# PFC_drivers_v1.net
KiCad netlist of a schematic drawn in EAGLE
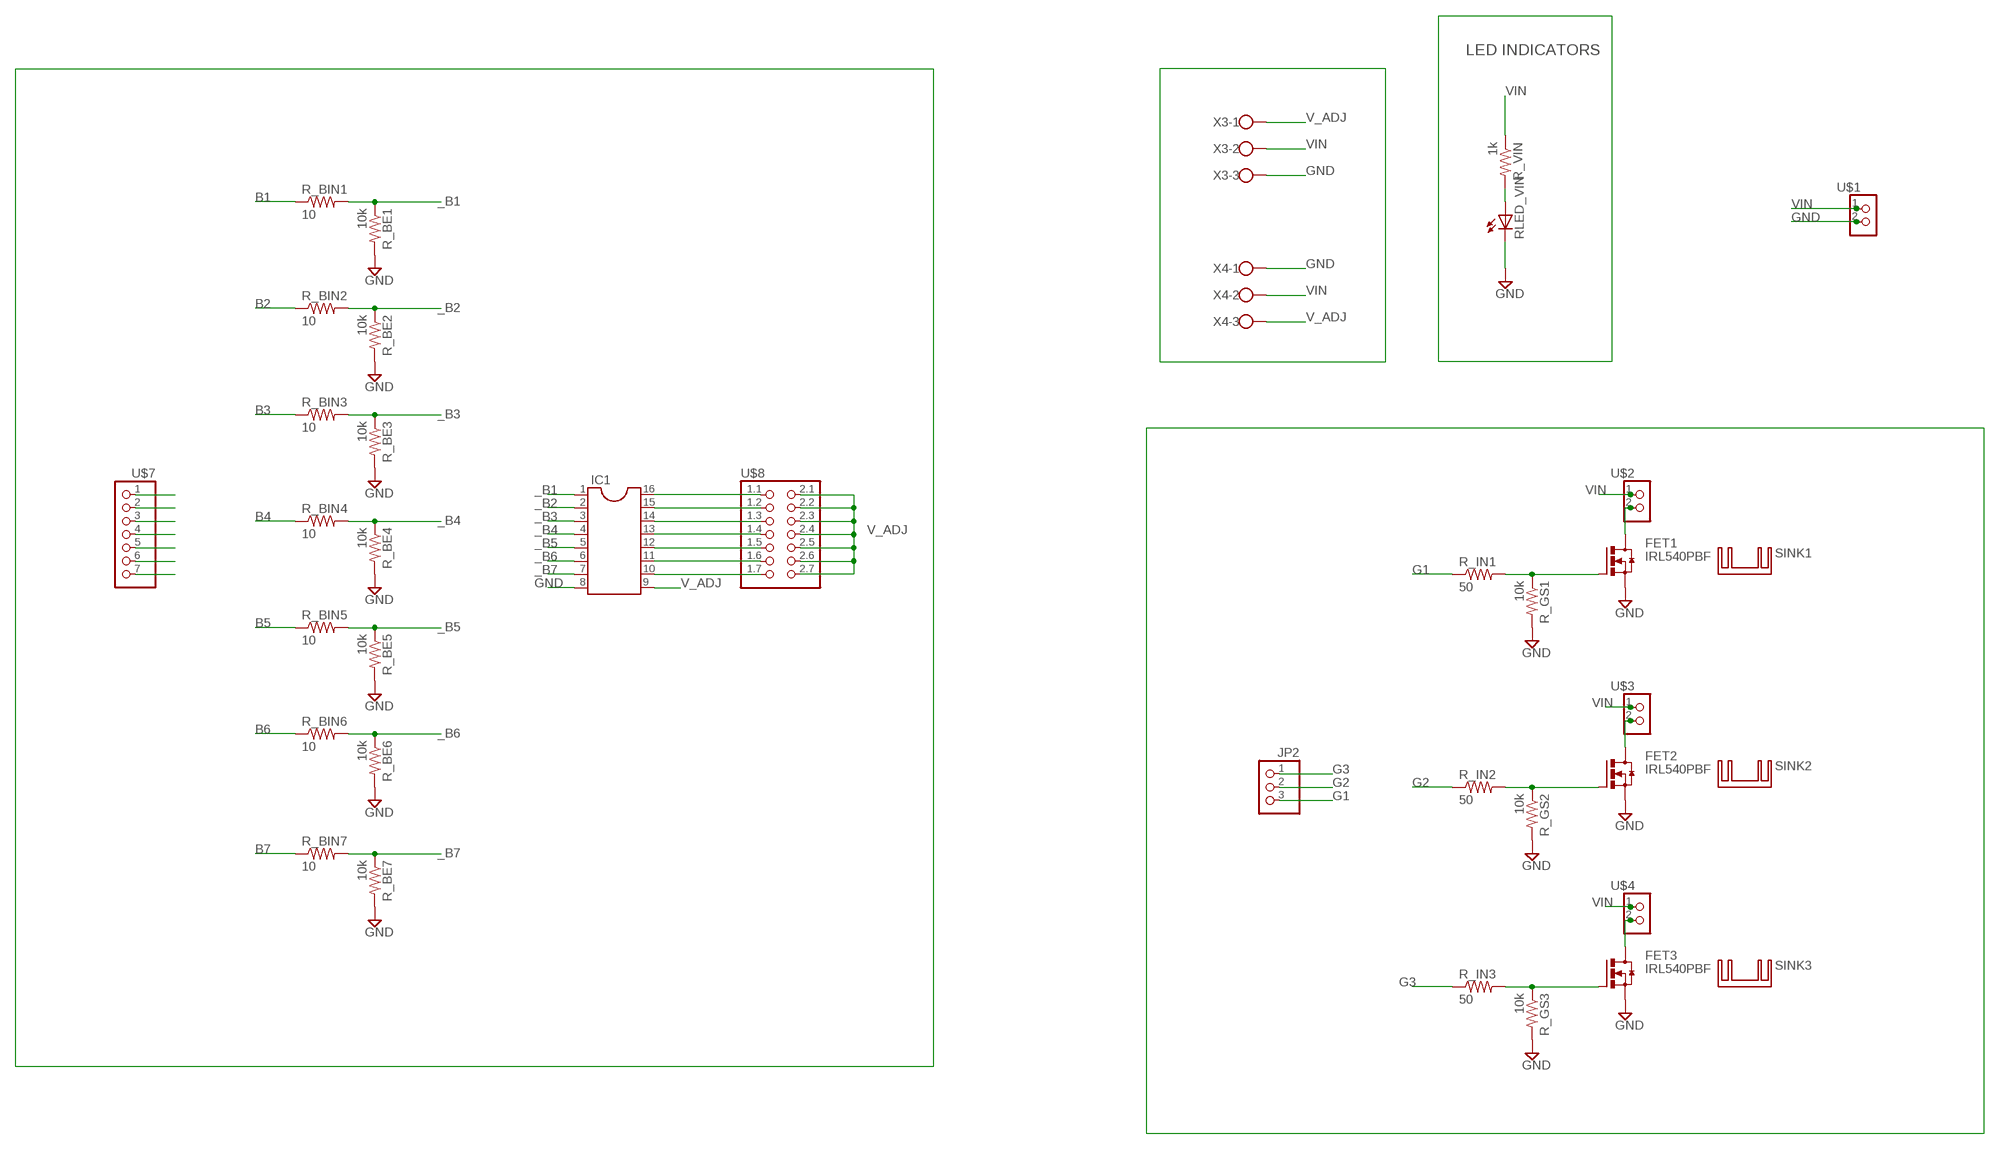
[diagram p0: schematic, sheet 1]

(export (version "E")
  (design (tool "Eeschema 10.0.6"))
  (components
    (comp (ref "FET1")
      (value "IRL540PBF")
      (footprint "eagle-import:TO220AV")
      (libsource (lib "eagle-import") (part "IRL540PBF"))
    )
    (comp (ref "FET2")
      (value "IRL540PBF")
      (footprint "eagle-import:TO220AV")
      (libsource (lib "eagle-import") (part "IRL540PBF"))
    )
    (comp (ref "FET3")
      (value "IRL540PBF")
      (footprint "eagle-import:TO220AV")
      (libsource (lib "eagle-import") (part "IRL540PBF"))
    )
    (comp (ref "IC1")
      (value "DIL16S")
      (footprint "eagle-import:SOCKET-16")
      (libsource (lib "eagle-import") (part "DIL16S"))
    )
    (comp (ref "JP2")
      (value "PINHD-1X3")
      (footprint "eagle-import:1X03")
      (libsource (lib "eagle-import") (part "PINHD-1X3"))
    )
    (comp (ref "RLED_VIN")
      (value "LEDCHIP-LED0603")
      (footprint "eagle-import:CHIP-LED0603")
      (libsource (lib "eagle-import") (part "LEDCHIP-LED0603"))
    )
    (comp (ref "R_BE1")
      (value "10k")
      (footprint "eagle-import:R0603")
      (libsource (lib "eagle-import") (part "R-US_R0603"))
    )
    (comp (ref "R_BE2")
      (value "10k")
      (footprint "eagle-import:R0603")
      (libsource (lib "eagle-import") (part "R-US_R0603"))
    )
    (comp (ref "R_BE3")
      (value "10k")
      (footprint "eagle-import:R0603")
      (libsource (lib "eagle-import") (part "R-US_R0603"))
    )
    (comp (ref "R_BE4")
      (value "10k")
      (footprint "eagle-import:R0603")
      (libsource (lib "eagle-import") (part "R-US_R0603"))
    )
    (comp (ref "R_BE5")
      (value "10k")
      (footprint "eagle-import:R0603")
      (libsource (lib "eagle-import") (part "R-US_R0603"))
    )
    (comp (ref "R_BE6")
      (value "10k")
      (footprint "eagle-import:R0603")
      (libsource (lib "eagle-import") (part "R-US_R0603"))
    )
    (comp (ref "R_BE7")
      (value "10k")
      (footprint "eagle-import:R0603")
      (libsource (lib "eagle-import") (part "R-US_R0603"))
    )
    (comp (ref "R_BIN1")
      (value "10")
      (footprint "eagle-import:R0603")
      (libsource (lib "eagle-import") (part "R-US_R0603"))
    )
    (comp (ref "R_BIN2")
      (value "10")
      (footprint "eagle-import:R0603")
      (libsource (lib "eagle-import") (part "R-US_R0603"))
    )
    (comp (ref "R_BIN3")
      (value "10")
      (footprint "eagle-import:R0603")
      (libsource (lib "eagle-import") (part "R-US_R0603"))
    )
    (comp (ref "R_BIN4")
      (value "10")
      (footprint "eagle-import:R0603")
      (libsource (lib "eagle-import") (part "R-US_R0603"))
    )
    (comp (ref "R_BIN5")
      (value "10")
      (footprint "eagle-import:R0603")
      (libsource (lib "eagle-import") (part "R-US_R0603"))
    )
    (comp (ref "R_BIN6")
      (value "10")
      (footprint "eagle-import:R0603")
      (libsource (lib "eagle-import") (part "R-US_R0603"))
    )
    (comp (ref "R_BIN7")
      (value "10")
      (footprint "eagle-import:R0603")
      (libsource (lib "eagle-import") (part "R-US_R0603"))
    )
    (comp (ref "R_GS1")
      (value "10k")
      (footprint "eagle-import:R0603")
      (libsource (lib "eagle-import") (part "R-US_R0603"))
    )
    (comp (ref "R_GS2")
      (value "10k")
      (footprint "eagle-import:R0603")
      (libsource (lib "eagle-import") (part "R-US_R0603"))
    )
    (comp (ref "R_GS3")
      (value "10k")
      (footprint "eagle-import:R0603")
      (libsource (lib "eagle-import") (part "R-US_R0603"))
    )
    (comp (ref "R_IN1")
      (value "50")
      (footprint "eagle-import:R0603")
      (libsource (lib "eagle-import") (part "R-US_R0603"))
    )
    (comp (ref "R_IN2")
      (value "50")
      (footprint "eagle-import:R0603")
      (libsource (lib "eagle-import") (part "R-US_R0603"))
    )
    (comp (ref "R_IN3")
      (value "50")
      (footprint "eagle-import:R0603")
      (libsource (lib "eagle-import") (part "R-US_R0603"))
    )
    (comp (ref "R_VIN")
      (value "1k")
      (footprint "eagle-import:R0603")
      (libsource (lib "eagle-import") (part "R-US_R0603"))
    )
    (comp (ref "SINK1")
      (value "FW1S")
      (footprint "eagle-import:FW1S")
      (libsource (lib "eagle-import") (part "FW1S"))
    )
    (comp (ref "SINK2")
      (value "FW1S")
      (footprint "eagle-import:FW1S")
      (libsource (lib "eagle-import") (part "FW1S"))
    )
    (comp (ref "SINK3")
      (value "FW1S")
      (footprint "eagle-import:FW1S")
      (libsource (lib "eagle-import") (part "FW1S"))
    )
    (comp (ref "U$1")
      (value "PINHD-2X1")
      (footprint "eagle-import:2X01")
      (libsource (lib "eagle-import") (part "PINHD-2X1"))
    )
    (comp (ref "U$2")
      (value "PINHD-2X1")
      (footprint "eagle-import:2X01")
      (libsource (lib "eagle-import") (part "PINHD-2X1"))
    )
    (comp (ref "U$3")
      (value "PINHD-2X1")
      (footprint "eagle-import:2X01")
      (libsource (lib "eagle-import") (part "PINHD-2X1"))
    )
    (comp (ref "U$4")
      (value "PINHD-2X1")
      (footprint "eagle-import:2X01")
      (libsource (lib "eagle-import") (part "PINHD-2X1"))
    )
    (comp (ref "U$7")
      (value "PINHD-1X7")
      (footprint "eagle-import:1X07")
      (libsource (lib "eagle-import") (part "PINHD-1X7"))
    )
    (comp (ref "U$8")
      (value "PINHD-2X7")
      (footprint "eagle-import:2X07-BIG")
      (libsource (lib "eagle-import") (part "PINHD-2X7"))
    )
    (comp (ref "X3")
      (value "W237-103")
      (footprint "eagle-import:W237-103")
      (fields (field (name "MPN") "237-103"))
      (libsource (lib "eagle-import") (part "W237-103"))
    )
    (comp (ref "X4")
      (value "W237-103")
      (footprint "eagle-import:W237-103")
      (fields (field (name "MPN") "237-103"))
      (libsource (lib "eagle-import") (part "W237-103"))
    )
  )
  (nets
    (net (code "1") (name "/B1") (class "Default")
      (node (ref "R_BIN1") (pin "1") (pinfunction "1_1") (pintype "passive"))
      (node (ref "U$7") (pin "1") (pinfunction "1_1") (pintype "passive"))
    )
    (net (code "2") (name "/B2") (class "Default")
      (node (ref "R_BIN2") (pin "1") (pinfunction "1_1") (pintype "passive"))
      (node (ref "U$7") (pin "2") (pinfunction "2_2") (pintype "passive"))
    )
    (net (code "3") (name "/B3") (class "Default")
      (node (ref "R_BIN3") (pin "1") (pinfunction "1_1") (pintype "passive"))
      (node (ref "U$7") (pin "3") (pinfunction "3_3") (pintype "passive"))
    )
    (net (code "4") (name "/B4") (class "Default")
      (node (ref "R_BIN4") (pin "1") (pinfunction "1_1") (pintype "passive"))
      (node (ref "U$7") (pin "4") (pinfunction "4_4") (pintype "passive"))
    )
    (net (code "5") (name "/B5") (class "Default")
      (node (ref "R_BIN5") (pin "1") (pinfunction "1_1") (pintype "passive"))
      (node (ref "U$7") (pin "5") (pinfunction "5_5") (pintype "passive"))
    )
    (net (code "6") (name "/B6") (class "Default")
      (node (ref "R_BIN6") (pin "1") (pinfunction "1_1") (pintype "passive"))
      (node (ref "U$7") (pin "6") (pinfunction "6_6") (pintype "passive"))
    )
    (net (code "7") (name "/B7") (class "Default")
      (node (ref "R_BIN7") (pin "1") (pinfunction "1_1") (pintype "passive"))
      (node (ref "U$7") (pin "7") (pinfunction "7_7") (pintype "passive"))
    )
    (net (code "8") (name "/G1") (class "Default")
      (node (ref "JP2") (pin "3") (pinfunction "3_3") (pintype "passive"))
      (node (ref "R_IN1") (pin "1") (pinfunction "1_1") (pintype "passive"))
    )
    (net (code "9") (name "/G2") (class "Default")
      (node (ref "JP2") (pin "2") (pinfunction "2_2") (pintype "passive"))
      (node (ref "R_IN2") (pin "1") (pinfunction "1_1") (pintype "passive"))
    )
    (net (code "10") (name "/G3") (class "Default")
      (node (ref "JP2") (pin "1") (pinfunction "1_1") (pintype "passive"))
      (node (ref "R_IN3") (pin "1") (pinfunction "1_1") (pintype "passive"))
    )
    (net (code "11") (name "/VIN") (class "Default")
      (node (ref "R_VIN") (pin "1") (pinfunction "1_1") (pintype "passive"))
      (node (ref "U$1") (pin "1") (pinfunction "1_1") (pintype "passive"))
      (node (ref "U$2") (pin "1") (pinfunction "1_1") (pintype "passive"))
      (node (ref "U$3") (pin "1") (pinfunction "1_1") (pintype "passive"))
      (node (ref "U$4") (pin "1") (pinfunction "1_1") (pintype "passive"))
      (node (ref "X3") (pin "2") (pinfunction "KL_2") (pintype "passive"))
      (node (ref "X4") (pin "2") (pinfunction "KL_2") (pintype "passive"))
    )
    (net (code "12") (name "/V_ADJ") (class "Default")
      (node (ref "IC1") (pin "9") (pinfunction "9_9") (pintype "passive"))
      (node (ref "U$8") (pin "2.1") (pinfunction "2.1_2.1") (pintype "passive"))
      (node (ref "U$8") (pin "2.2") (pinfunction "2.2_2.2") (pintype "passive"))
      (node (ref "U$8") (pin "2.3") (pinfunction "2.3_2.3") (pintype "passive"))
      (node (ref "U$8") (pin "2.4") (pinfunction "2.4_2.4") (pintype "passive"))
      (node (ref "U$8") (pin "2.5") (pinfunction "2.5_2.5") (pintype "passive"))
      (node (ref "U$8") (pin "2.6") (pinfunction "2.6_2.6") (pintype "passive"))
      (node (ref "U$8") (pin "2.7") (pinfunction "2.7_2.7") (pintype "passive"))
      (node (ref "X3") (pin "1") (pinfunction "KL_1") (pintype "passive"))
      (node (ref "X4") (pin "3") (pinfunction "KL_3") (pintype "passive"))
    )
    (net (code "13") (name "/_B1") (class "Default")
      (node (ref "IC1") (pin "1") (pinfunction "1_1") (pintype "passive"))
      (node (ref "R_BE1") (pin "1") (pinfunction "1_1") (pintype "passive"))
      (node (ref "R_BIN1") (pin "2") (pinfunction "2_2") (pintype "passive"))
    )
    (net (code "14") (name "/_B2") (class "Default")
      (node (ref "IC1") (pin "2") (pinfunction "2_2") (pintype "passive"))
      (node (ref "R_BE2") (pin "1") (pinfunction "1_1") (pintype "passive"))
      (node (ref "R_BIN2") (pin "2") (pinfunction "2_2") (pintype "passive"))
    )
    (net (code "15") (name "/_B3") (class "Default")
      (node (ref "IC1") (pin "3") (pinfunction "3_3") (pintype "passive"))
      (node (ref "R_BE3") (pin "1") (pinfunction "1_1") (pintype "passive"))
      (node (ref "R_BIN3") (pin "2") (pinfunction "2_2") (pintype "passive"))
    )
    (net (code "16") (name "/_B4") (class "Default")
      (node (ref "IC1") (pin "4") (pinfunction "4_4") (pintype "passive"))
      (node (ref "R_BE4") (pin "1") (pinfunction "1_1") (pintype "passive"))
      (node (ref "R_BIN4") (pin "2") (pinfunction "2_2") (pintype "passive"))
    )
    (net (code "17") (name "/_B5") (class "Default")
      (node (ref "IC1") (pin "5") (pinfunction "5_5") (pintype "passive"))
      (node (ref "R_BE5") (pin "1") (pinfunction "1_1") (pintype "passive"))
      (node (ref "R_BIN5") (pin "2") (pinfunction "2_2") (pintype "passive"))
    )
    (net (code "18") (name "/_B6") (class "Default")
      (node (ref "IC1") (pin "6") (pinfunction "6_6") (pintype "passive"))
      (node (ref "R_BE6") (pin "1") (pinfunction "1_1") (pintype "passive"))
      (node (ref "R_BIN6") (pin "2") (pinfunction "2_2") (pintype "passive"))
    )
    (net (code "19") (name "/_B7") (class "Default")
      (node (ref "IC1") (pin "7") (pinfunction "7_7") (pintype "passive"))
      (node (ref "R_BE7") (pin "1") (pinfunction "1_1") (pintype "passive"))
      (node (ref "R_BIN7") (pin "2") (pinfunction "2_2") (pintype "passive"))
    )
    (net (code "20") (name "GND") (class "Default")
      (node (ref "FET1") (pin "E") (pinfunction "S_E") (pintype "passive"))
      (node (ref "FET2") (pin "E") (pinfunction "S_E") (pintype "passive"))
      (node (ref "FET3") (pin "E") (pinfunction "S_E") (pintype "passive"))
      (node (ref "IC1") (pin "8") (pinfunction "8_8") (pintype "passive"))
      (node (ref "RLED_VIN") (pin "C") (pinfunction "C_C") (pintype "passive"))
      (node (ref "R_BE1") (pin "2") (pinfunction "2_2") (pintype "passive"))
      (node (ref "R_BE2") (pin "2") (pinfunction "2_2") (pintype "passive"))
      (node (ref "R_BE3") (pin "2") (pinfunction "2_2") (pintype "passive"))
      (node (ref "R_BE4") (pin "2") (pinfunction "2_2") (pintype "passive"))
      (node (ref "R_BE5") (pin "2") (pinfunction "2_2") (pintype "passive"))
      (node (ref "R_BE6") (pin "2") (pinfunction "2_2") (pintype "passive"))
      (node (ref "R_BE7") (pin "2") (pinfunction "2_2") (pintype "passive"))
      (node (ref "R_GS1") (pin "2") (pinfunction "2_2") (pintype "passive"))
      (node (ref "R_GS2") (pin "2") (pinfunction "2_2") (pintype "passive"))
      (node (ref "R_GS3") (pin "2") (pinfunction "2_2") (pintype "passive"))
      (node (ref "U$1") (pin "2") (pinfunction "3_2") (pintype "passive"))
      (node (ref "X3") (pin "3") (pinfunction "KL_3") (pintype "passive"))
      (node (ref "X4") (pin "1") (pinfunction "KL_1") (pintype "passive"))
    )
    (net (code "21") (name "Net-(FET1-D)") (class "Default")
      (node (ref "FET1") (pin "C") (pinfunction "D_C") (pintype "passive"))
      (node (ref "U$2") (pin "2") (pinfunction "3_2") (pintype "passive"))
    )
    (net (code "22") (name "Net-(FET1-G)") (class "Default")
      (node (ref "FET1") (pin "B") (pinfunction "G_B") (pintype "passive"))
      (node (ref "R_GS1") (pin "1") (pinfunction "1_1") (pintype "passive"))
      (node (ref "R_IN1") (pin "2") (pinfunction "2_2") (pintype "passive"))
    )
    (net (code "23") (name "Net-(FET2-D)") (class "Default")
      (node (ref "FET2") (pin "C") (pinfunction "D_C") (pintype "passive"))
      (node (ref "U$3") (pin "2") (pinfunction "3_2") (pintype "passive"))
    )
    (net (code "24") (name "Net-(FET2-G)") (class "Default")
      (node (ref "FET2") (pin "B") (pinfunction "G_B") (pintype "passive"))
      (node (ref "R_GS2") (pin "1") (pinfunction "1_1") (pintype "passive"))
      (node (ref "R_IN2") (pin "2") (pinfunction "2_2") (pintype "passive"))
    )
    (net (code "25") (name "Net-(FET3-D)") (class "Default")
      (node (ref "FET3") (pin "C") (pinfunction "D_C") (pintype "passive"))
      (node (ref "U$4") (pin "2") (pinfunction "3_2") (pintype "passive"))
    )
    (net (code "26") (name "Net-(FET3-G)") (class "Default")
      (node (ref "FET3") (pin "B") (pinfunction "G_B") (pintype "passive"))
      (node (ref "R_GS3") (pin "1") (pinfunction "1_1") (pintype "passive"))
      (node (ref "R_IN3") (pin "2") (pinfunction "2_2") (pintype "passive"))
    )
    (net (code "27") (name "Net-(IC1-Pad10)") (class "Default")
      (node (ref "IC1") (pin "10") (pinfunction "10_10") (pintype "passive"))
      (node (ref "U$8") (pin "1.7") (pinfunction "1.7_1.7") (pintype "passive"))
    )
    (net (code "28") (name "Net-(IC1-Pad11)") (class "Default")
      (node (ref "IC1") (pin "11") (pinfunction "11_11") (pintype "passive"))
      (node (ref "U$8") (pin "1.6") (pinfunction "1.6_1.6") (pintype "passive"))
    )
    (net (code "29") (name "Net-(IC1-Pad12)") (class "Default")
      (node (ref "IC1") (pin "12") (pinfunction "12_12") (pintype "passive"))
      (node (ref "U$8") (pin "1.5") (pinfunction "1.5_1.5") (pintype "passive"))
    )
    (net (code "30") (name "Net-(IC1-Pad13)") (class "Default")
      (node (ref "IC1") (pin "13") (pinfunction "13_13") (pintype "passive"))
      (node (ref "U$8") (pin "1.4") (pinfunction "1.4_1.4") (pintype "passive"))
    )
    (net (code "31") (name "Net-(IC1-Pad14)") (class "Default")
      (node (ref "IC1") (pin "14") (pinfunction "14_14") (pintype "passive"))
      (node (ref "U$8") (pin "1.3") (pinfunction "1.3_1.3") (pintype "passive"))
    )
    (net (code "32") (name "Net-(IC1-Pad15)") (class "Default")
      (node (ref "IC1") (pin "15") (pinfunction "15_15") (pintype "passive"))
      (node (ref "U$8") (pin "1.2") (pinfunction "1.2_1.2") (pintype "passive"))
    )
    (net (code "33") (name "Net-(IC1-Pad16)") (class "Default")
      (node (ref "IC1") (pin "16") (pinfunction "16_16") (pintype "passive"))
      (node (ref "U$8") (pin "1.1") (pinfunction "1.1_1.1") (pintype "passive"))
    )
    (net (code "34") (name "Net-(RLED_VIN-PadA)") (class "Default")
      (node (ref "RLED_VIN") (pin "A") (pinfunction "A_A") (pintype "passive"))
      (node (ref "R_VIN") (pin "2") (pinfunction "2_2") (pintype "passive"))
    )
  )
)
